# nixie_arduino.net
KiCad netlist of a schematic drawn in EAGLE
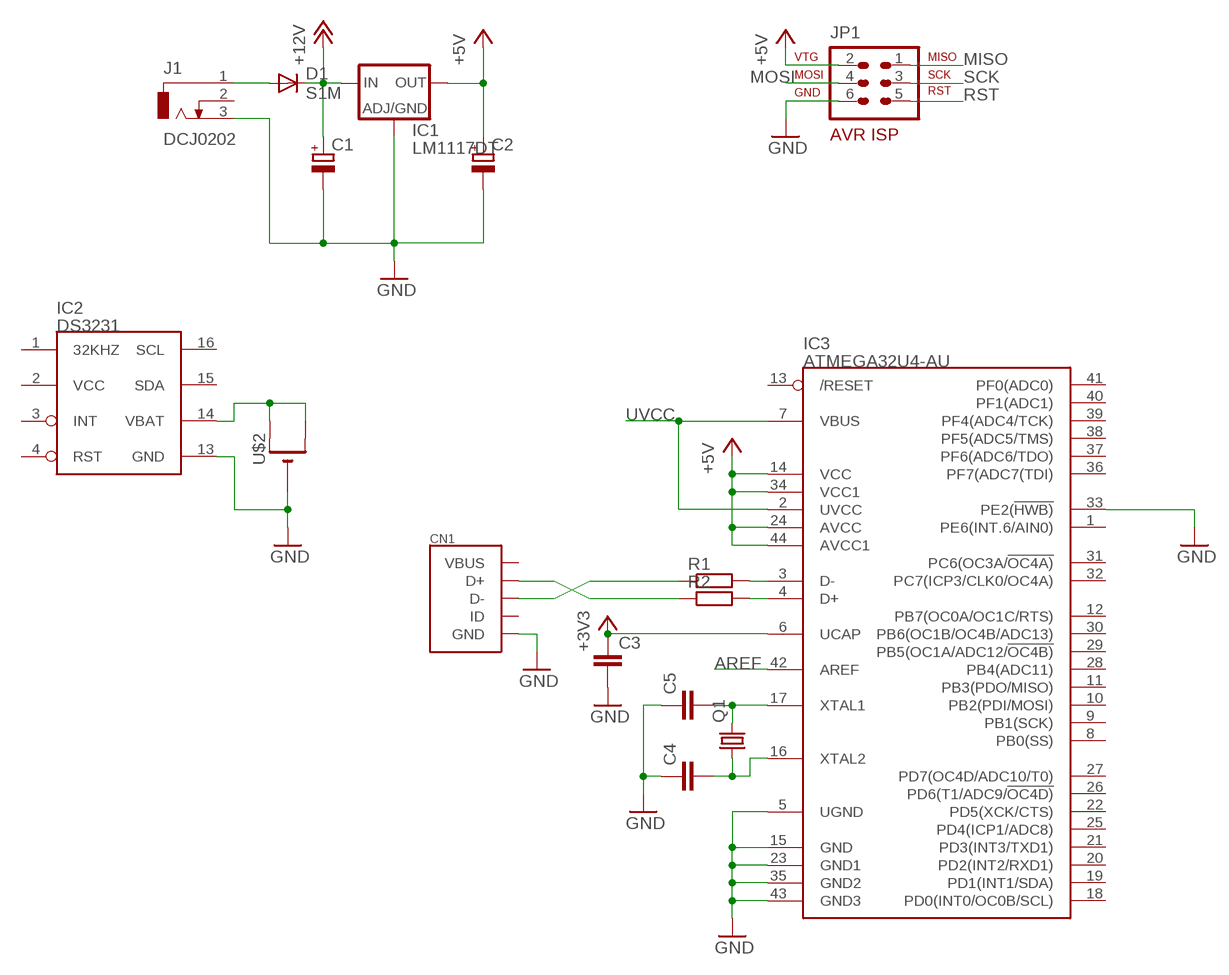
[diagram p0: schematic, sheet 1]

(export (version "E")
  (design (tool "Eeschema 10.0.6"))
  (components
    (comp (ref "C1")
      (value "CPOL-EUD")
      (footprint "eagle-import:PANASONIC_D")
      (libsource (lib "eagle-import") (part "CPOL-EUD"))
    )
    (comp (ref "C2")
      (value "CPOL-EUD")
      (footprint "eagle-import:PANASONIC_D")
      (libsource (lib "eagle-import") (part "CPOL-EUD"))
    )
    (comp (ref "C3")
      (value "C-EUC0805K")
      (footprint "eagle-import:C0805K")
      (libsource (lib "eagle-import") (part "C-EUC0805K"))
    )
    (comp (ref "C4")
      (value "C-EUC0805K")
      (footprint "eagle-import:C0805K")
      (libsource (lib "eagle-import") (part "C-EUC0805K"))
    )
    (comp (ref "C5")
      (value "C-EUC0805K")
      (footprint "eagle-import:C0805K")
      (libsource (lib "eagle-import") (part "C-EUC0805K"))
    )
    (comp (ref "CN1")
      (value "USBMINIB")
      (footprint "eagle-import:USB-MINIB")
      (libsource (lib "eagle-import") (part "USBMINIB"))
    )
    (comp (ref "D1")
      (value "S1M")
      (footprint "eagle-import:DO-214AC")
      (libsource (lib "eagle-import") (part "S1M"))
    )
    (comp (ref "IC1")
      (value "LM1117DT")
      (footprint "eagle-import:DPACK")
      (libsource (lib "eagle-import") (part "LM1117DT"))
    )
    (comp (ref "IC2")
      (value "DS3231")
      (footprint "eagle-import:SO16")
      (libsource (lib "eagle-import") (part "DS3231"))
    )
    (comp (ref "IC3")
      (value "ATMEGA32U4-AU")
      (footprint "eagle-import:TQFP44")
      (libsource (lib "eagle-import") (part "ATMEGA32U4-AU"))
    )
    (comp (ref "J1")
      (value "DCJ0202")
      (footprint "eagle-import:DCJ0202A")
      (libsource (lib "eagle-import") (part "DCJ0202"))
    )
    (comp (ref "JP1")
      (value "AVR-ISP-6")
      (footprint "eagle-import:AVR-ISP-6")
      (libsource (lib "eagle-import") (part "nixie_tube_AVR-ISP-6"))
    )
    (comp (ref "Q1")
      (value "CRYSTALHC49UP")
      (footprint "eagle-import:HC49UP")
      (libsource (lib "eagle-import") (part "CRYSTALHC49UP"))
    )
    (comp (ref "R1")
      (value "R-EU_R0805")
      (footprint "eagle-import:R0805")
      (libsource (lib "eagle-import") (part "R-EU_R0805"))
    )
    (comp (ref "R2")
      (value "R-EU_R0805")
      (footprint "eagle-import:R0805")
      (libsource (lib "eagle-import") (part "R-EU_R0805"))
    )
    (comp (ref "U$2")
      (value "CR1220SMT")
      (footprint "eagle-import:CR1220-SMD")
      (libsource (lib "eagle-import") (part "CR1220SMT"))
    )
  )
  (nets
    (net (code "1") (name "+3V3") (class "Default")
      (node (ref "C3") (pin "1") (pinfunction "1_1") (pintype "passive"))
      (node (ref "IC3") (pin "6") (pinfunction "UCAP_6") (pintype "bidirectional"))
    )
    (net (code "2") (name "+5V") (class "Default")
      (node (ref "C2") (pin "+") (pinfunction "+_+") (pintype "passive"))
      (node (ref "IC1") (pin "4") (pinfunction "OUT_4") (pintype "passive"))
      (node (ref "IC3") (pin "14") (pinfunction "VCC_14") (pintype "bidirectional"))
      (node (ref "IC3") (pin "24") (pinfunction "AVCC_24") (pintype "bidirectional"))
      (node (ref "IC3") (pin "34") (pinfunction "VCC1_34") (pintype "bidirectional"))
      (node (ref "IC3") (pin "44") (pinfunction "AVCC1_44") (pintype "bidirectional"))
      (node (ref "JP1") (pin "2") (pinfunction "VTG_2") (pintype "passive"))
    )
    (net (code "3") (name "+12V") (class "Default")
      (node (ref "C1") (pin "+") (pinfunction "+_+") (pintype "passive"))
      (node (ref "D1") (pin "C") (pinfunction "C_C") (pintype "passive"))
      (node (ref "IC1") (pin "3") (pinfunction "IN_3") (pintype "input"))
    )
    (net (code "4") (name "/AREF") (class "Default")
      (node (ref "IC3") (pin "42") (pinfunction "AREF_42") (pintype "bidirectional"))
    )
    (net (code "5") (name "/MISO") (class "Default")
      (node (ref "JP1") (pin "1") (pinfunction "MISO_1") (pintype "passive"))
    )
    (net (code "6") (name "/MOSI") (class "Default")
      (node (ref "JP1") (pin "4") (pinfunction "MOSI_4") (pintype "passive"))
    )
    (net (code "7") (name "/RST") (class "Default")
      (node (ref "JP1") (pin "5") (pinfunction "RST_5") (pintype "passive"))
    )
    (net (code "8") (name "/SCK") (class "Default")
      (node (ref "JP1") (pin "3") (pinfunction "SCK_3") (pintype "passive"))
    )
    (net (code "9") (name "/UVCC") (class "Default")
      (node (ref "IC3") (pin "2") (pinfunction "UVCC_2") (pintype "bidirectional"))
      (node (ref "IC3") (pin "7") (pinfunction "VBUS_7") (pintype "bidirectional"))
    )
    (net (code "10") (name "/VBUS") (class "Default")
      (node (ref "CN1") (pin "VBUS") (pinfunction "VBUS_VBUS") (pintype "power_in"))
    )
    (net (code "11") (name "GND") (class "Default")
      (node (ref "C1") (pin "-") (pinfunction "-_-") (pintype "passive"))
      (node (ref "C2") (pin "-") (pinfunction "-_-") (pintype "passive"))
      (node (ref "C3") (pin "2") (pinfunction "2_2") (pintype "passive"))
      (node (ref "C4") (pin "1") (pinfunction "1_1") (pintype "passive"))
      (node (ref "C5") (pin "1") (pinfunction "1_1") (pintype "passive"))
      (node (ref "CN1") (pin "GND") (pinfunction "GND_GND") (pintype "power_in"))
      (node (ref "IC1") (pin "1") (pinfunction "ADJ_1") (pintype "input"))
      (node (ref "IC2") (pin "13") (pinfunction "GND_13") (pintype "bidirectional"))
      (node (ref "IC3") (pin "15") (pinfunction "GND_15") (pintype "bidirectional"))
      (node (ref "IC3") (pin "23") (pinfunction "GND1_23") (pintype "bidirectional"))
      (node (ref "IC3") (pin "33") (pinfunction "PE2(~{HWB})_33") (pintype "bidirectional"))
      (node (ref "IC3") (pin "35") (pinfunction "GND2_35") (pintype "bidirectional"))
      (node (ref "IC3") (pin "43") (pinfunction "GND3_43") (pintype "bidirectional"))
      (node (ref "IC3") (pin "5") (pinfunction "UGND_5") (pintype "bidirectional"))
      (node (ref "J1") (pin "3") (pinfunction "3_3") (pintype "passive"))
      (node (ref "JP1") (pin "6") (pinfunction "GND_6") (pintype "passive"))
      (node (ref "U$2") (pin "-") (pinfunction "-_-") (pintype "passive"))
    )
    (net (code "12") (name "Net-(CN1-PadD+)") (class "Default")
      (node (ref "CN1") (pin "D+") (pinfunction "D+_D+") (pintype "bidirectional"))
      (node (ref "R2") (pin "1") (pinfunction "1_1") (pintype "passive"))
    )
    (net (code "13") (name "Net-(CN1-PadD-)") (class "Default")
      (node (ref "CN1") (pin "D-") (pinfunction "D-_D-") (pintype "bidirectional"))
      (node (ref "R1") (pin "1") (pinfunction "1_1") (pintype "passive"))
    )
    (net (code "14") (name "Net-(D1-PadA)") (class "Default")
      (node (ref "D1") (pin "A") (pinfunction "A_A") (pintype "passive"))
      (node (ref "J1") (pin "1") (pinfunction "1_1") (pintype "passive"))
    )
    (net (code "15") (name "Net-(IC2-VBAT)") (class "Default")
      (node (ref "IC2") (pin "14") (pinfunction "VBAT_14") (pintype "bidirectional"))
      (node (ref "U$2") (pin "+$1") (pinfunction "+_+$1") (pintype "passive"))
      (node (ref "U$2") (pin "+$2") (pinfunction "+1_+$2") (pintype "passive"))
    )
    (net (code "16") (name "Net-(IC3-D+)") (class "Default")
      (node (ref "IC3") (pin "4") (pinfunction "D+_4") (pintype "bidirectional"))
      (node (ref "R2") (pin "2") (pinfunction "2_2") (pintype "passive"))
    )
    (net (code "17") (name "Net-(IC3-D-)") (class "Default")
      (node (ref "IC3") (pin "3") (pinfunction "D-_3") (pintype "bidirectional"))
      (node (ref "R1") (pin "2") (pinfunction "2_2") (pintype "passive"))
    )
    (net (code "18") (name "Net-(IC3-XTAL1)") (class "Default")
      (node (ref "C5") (pin "2") (pinfunction "2_2") (pintype "passive"))
      (node (ref "IC3") (pin "17") (pinfunction "XTAL1_17") (pintype "bidirectional"))
      (node (ref "Q1") (pin "2") (pinfunction "2_2") (pintype "passive"))
    )
    (net (code "19") (name "Net-(IC3-XTAL2)") (class "Default")
      (node (ref "C4") (pin "2") (pinfunction "2_2") (pintype "passive"))
      (node (ref "IC3") (pin "16") (pinfunction "XTAL2_16") (pintype "bidirectional"))
      (node (ref "Q1") (pin "1") (pinfunction "1_1") (pintype "passive"))
    )
    (net (code "20") (name "unconnected-(CN1-PadID)") (class "Default")
      (node (ref "CN1") (pin "ID") (pinfunction "ID_ID") (pintype "bidirectional"))
    )
    (net (code "21") (name "unconnected-(IC2-32KHZ-Pad1)") (class "Default")
      (node (ref "IC2") (pin "1") (pinfunction "32KHZ_1") (pintype "output"))
    )
    (net (code "22") (name "unconnected-(IC2-INT-Pad3)") (class "Default")
      (node (ref "IC2") (pin "3") (pinfunction "INT_3") (pintype "bidirectional"))
    )
    (net (code "23") (name "unconnected-(IC2-RST-Pad4)") (class "Default")
      (node (ref "IC2") (pin "4") (pinfunction "RST_4") (pintype "bidirectional"))
    )
    (net (code "24") (name "unconnected-(IC2-SCL-Pad16)") (class "Default")
      (node (ref "IC2") (pin "16") (pinfunction "SCL_16") (pintype "bidirectional"))
    )
    (net (code "25") (name "unconnected-(IC2-SDA-Pad15)") (class "Default")
      (node (ref "IC2") (pin "15") (pinfunction "SDA_15") (pintype "bidirectional"))
    )
    (net (code "26") (name "unconnected-(IC2-VCC-Pad2)") (class "Default")
      (node (ref "IC2") (pin "2") (pinfunction "VCC_2") (pintype "input"))
    )
    (net (code "27") (name "unconnected-(IC3-PB0(SS)-Pad8)") (class "Default")
      (node (ref "IC3") (pin "8") (pinfunction "PB0(SS)_8") (pintype "bidirectional"))
    )
    (net (code "28") (name "unconnected-(IC3-PB1(SCK)-Pad9)") (class "Default")
      (node (ref "IC3") (pin "9") (pinfunction "PB1(SCK)_9") (pintype "bidirectional"))
    )
    (net (code "29") (name "unconnected-(IC3-PB2(PDI{slash}MOSI)-Pad10)") (class "Default")
      (node (ref "IC3") (pin "10") (pinfunction "PB2(PDI/MOSI)_10") (pintype "bidirectional"))
    )
    (net (code "30") (name "unconnected-(IC3-PB3(PDO{slash}MISO)-Pad11)") (class "Default")
      (node (ref "IC3") (pin "11") (pinfunction "PB3(PDO/MISO)_11") (pintype "bidirectional"))
    )
    (net (code "31") (name "unconnected-(IC3-PB4(ADC11)-Pad28)") (class "Default")
      (node (ref "IC3") (pin "28") (pinfunction "PB4(ADC11)_28") (pintype "bidirectional"))
    )
    (net (code "32") (name "unconnected-(IC3-PB5(OC1A{slash}ADC12{slash}~{OC4B})-Pad29)") (class "Default")
      (node (ref "IC3") (pin "29") (pinfunction "PB5(OC1A/ADC12/~{OC4B})_29") (pintype "bidirectional"))
    )
    (net (code "33") (name "unconnected-(IC3-PB6(OC1B{slash}OC4B{slash}ADC13)-Pad30)") (class "Default")
      (node (ref "IC3") (pin "30") (pinfunction "PB6(OC1B/OC4B/ADC13)_30") (pintype "bidirectional"))
    )
    (net (code "34") (name "unconnected-(IC3-PB7(OC0A{slash}OC1C{slash}RTS)-Pad12)") (class "Default")
      (node (ref "IC3") (pin "12") (pinfunction "PB7(OC0A/OC1C/RTS)_12") (pintype "bidirectional"))
    )
    (net (code "35") (name "unconnected-(IC3-PC6(OC3A{slash}~{OC4A})-Pad31)") (class "Default")
      (node (ref "IC3") (pin "31") (pinfunction "PC6(OC3A/~{OC4A})_31") (pintype "bidirectional"))
    )
    (net (code "36") (name "unconnected-(IC3-PC7(ICP3{slash}CLK0{slash}OC4A)-Pad32)") (class "Default")
      (node (ref "IC3") (pin "32") (pinfunction "PC7(ICP3/CLK0/OC4A)_32") (pintype "bidirectional"))
    )
    (net (code "37") (name "unconnected-(IC3-PD0(INT0{slash}OC0B{slash}SCL)-Pad18)") (class "Default")
      (node (ref "IC3") (pin "18") (pinfunction "PD0(INT0/OC0B/SCL)_18") (pintype "bidirectional"))
    )
    (net (code "38") (name "unconnected-(IC3-PD1(INT1{slash}SDA)-Pad19)") (class "Default")
      (node (ref "IC3") (pin "19") (pinfunction "PD1(INT1/SDA)_19") (pintype "bidirectional"))
    )
    (net (code "39") (name "unconnected-(IC3-PD2(INT2{slash}RXD1)-Pad20)") (class "Default")
      (node (ref "IC3") (pin "20") (pinfunction "PD2(INT2/RXD1)_20") (pintype "bidirectional"))
    )
    (net (code "40") (name "unconnected-(IC3-PD3(INT3{slash}TXD1)-Pad21)") (class "Default")
      (node (ref "IC3") (pin "21") (pinfunction "PD3(INT3/TXD1)_21") (pintype "bidirectional"))
    )
    (net (code "41") (name "unconnected-(IC3-PD4(ICP1{slash}ADC8)-Pad25)") (class "Default")
      (node (ref "IC3") (pin "25") (pinfunction "PD4(ICP1/ADC8)_25") (pintype "bidirectional"))
    )
    (net (code "42") (name "unconnected-(IC3-PD5(XCK{slash}CTS)-Pad22)") (class "Default")
      (node (ref "IC3") (pin "22") (pinfunction "PD5(XCK/CTS)_22") (pintype "bidirectional"))
    )
    (net (code "43") (name "unconnected-(IC3-PD6(T1{slash}ADC9{slash}~{OC4D})-Pad26)") (class "Default")
      (node (ref "IC3") (pin "26") (pinfunction "PD6(T1/ADC9/~{OC4D})_26") (pintype "bidirectional"))
    )
    (net (code "44") (name "unconnected-(IC3-PD7(OC4D{slash}ADC10{slash}T0)-Pad27)") (class "Default")
      (node (ref "IC3") (pin "27") (pinfunction "PD7(OC4D/ADC10/T0)_27") (pintype "bidirectional"))
    )
    (net (code "45") (name "unconnected-(IC3-PE6(INT.6{slash}AIN0)-Pad1)") (class "Default")
      (node (ref "IC3") (pin "1") (pinfunction "PE6(INT.6/AIN0)_1") (pintype "bidirectional"))
    )
    (net (code "46") (name "unconnected-(IC3-PF0(ADC0)-Pad41)") (class "Default")
      (node (ref "IC3") (pin "41") (pinfunction "PF0(ADC0)_41") (pintype "bidirectional"))
    )
    (net (code "47") (name "unconnected-(IC3-PF1(ADC1)-Pad40)") (class "Default")
      (node (ref "IC3") (pin "40") (pinfunction "PF1(ADC1)_40") (pintype "bidirectional"))
    )
    (net (code "48") (name "unconnected-(IC3-PF4(ADC4{slash}TCK)-Pad39)") (class "Default")
      (node (ref "IC3") (pin "39") (pinfunction "PF4(ADC4/TCK)_39") (pintype "bidirectional"))
    )
    (net (code "49") (name "unconnected-(IC3-PF5(ADC5{slash}TMS)-Pad38)") (class "Default")
      (node (ref "IC3") (pin "38") (pinfunction "PF5(ADC5/TMS)_38") (pintype "bidirectional"))
    )
    (net (code "50") (name "unconnected-(IC3-PF6(ADC6{slash}TDO)-Pad37)") (class "Default")
      (node (ref "IC3") (pin "37") (pinfunction "PF6(ADC6/TDO)_37") (pintype "bidirectional"))
    )
    (net (code "51") (name "unconnected-(IC3-PF7(ADC7(TDI)-Pad36)") (class "Default")
      (node (ref "IC3") (pin "36") (pinfunction "PF7(ADC7(TDI)_36") (pintype "bidirectional"))
    )
    (net (code "52") (name "unconnected-(IC3-{slash}RESET-Pad13)") (class "Default")
      (node (ref "IC3") (pin "13") (pinfunction "/RESET_13") (pintype "bidirectional"))
    )
    (net (code "53") (name "unconnected-(J1-Pad2)") (class "Default")
      (node (ref "J1") (pin "2") (pinfunction "2_2") (pintype "passive"))
    )
  )
)
